# Auxiliary.net
KiCad netlist of a schematic drawn in Altium Designer
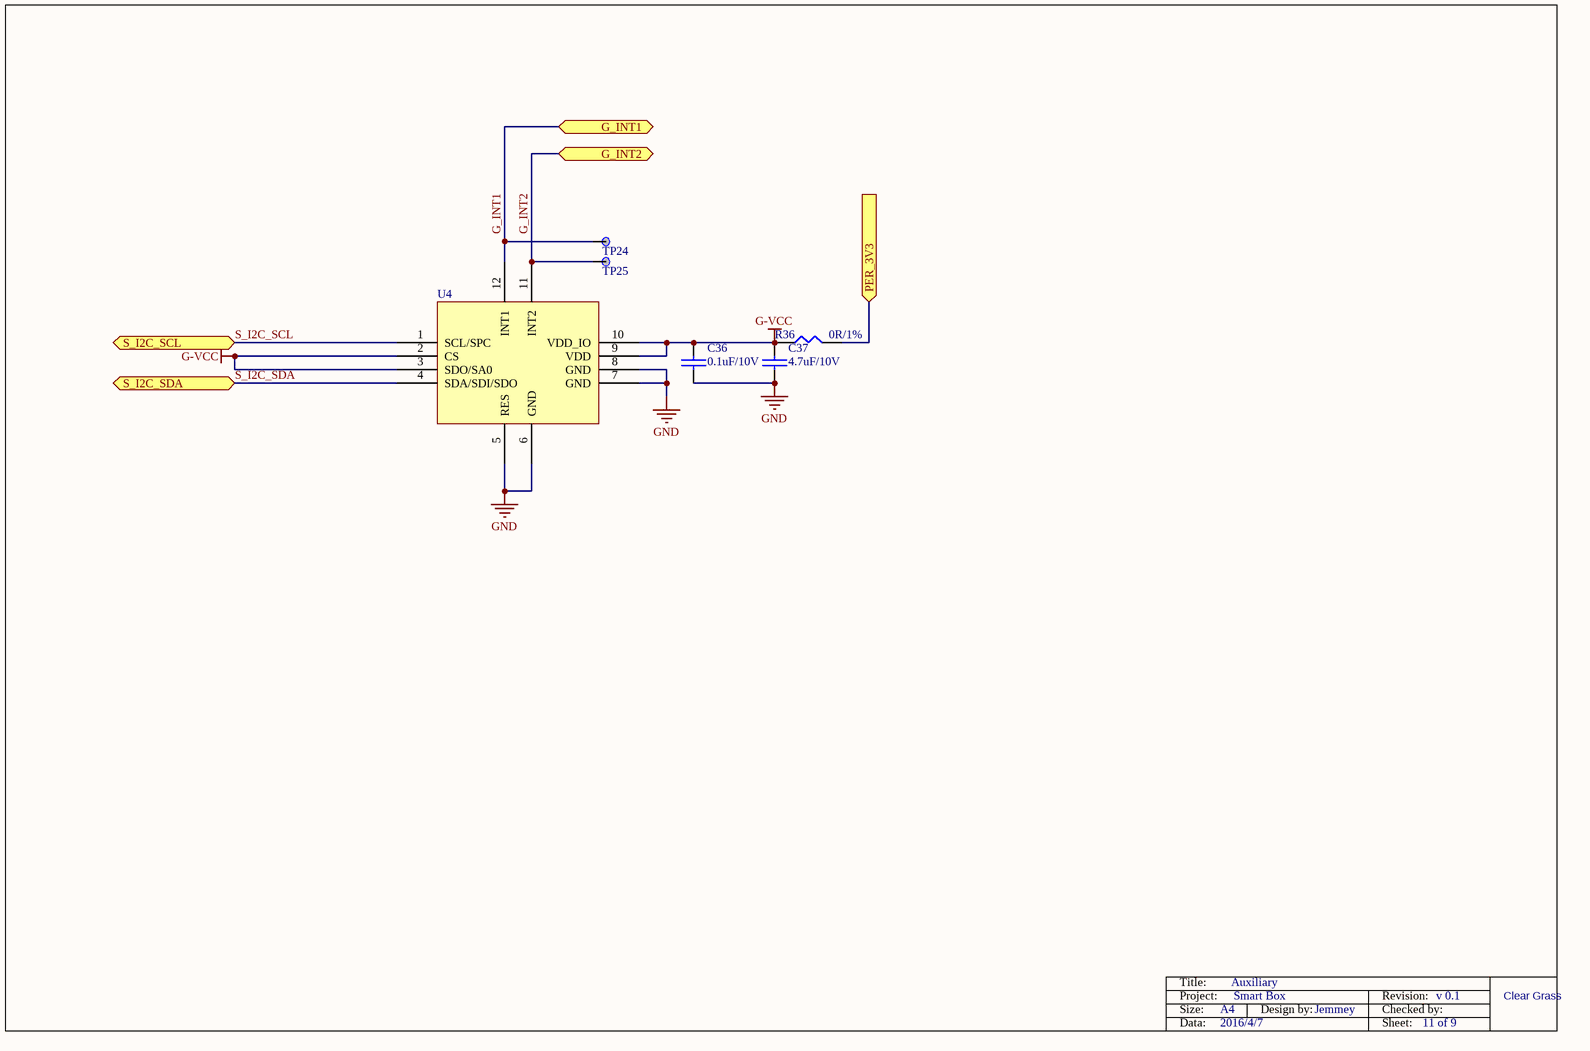
[diagram p0: Auxiliary.SchDoc]

(export (version "E")
  (design (tool "Eeschema 10.0.6"))
  (components
    (comp (ref "C36")
      (value "0.1uF/10V")
      (footprint "0402C")
      (description "厂家：Murata，型号：GRM155R71A104KA01D")
      (libsource (lib "*") (part "CAP"))
    )
    (comp (ref "C37")
      (value "4.7uF/10V")
      (footprint "0603C")
      (description "厂家：Murata，型号：GRM188R61A106KE69D")
      (libsource (lib "*") (part "CAP"))
    )
    (comp (ref "R36")
      (value "0R/1%")
      (footprint "0402R")
      (description "厂家：Yageo，型号：RC0402FR-0710KL")
      (libsource (lib "*") (part "RES1"))
    )
    (comp (ref "TP24") (value "TP") (footprint "TP_C40") (libsource (lib "Almos") (part "TP")))
    (comp (ref "TP25") (value "TP") (footprint "TP_C40") (libsource (lib "Almos") (part "TP")))
    (comp (ref "U4")
      (value "~")
      (description "厂家：ST，型号：LIS2DH12")
      (libsource (lib "Smart Box") (part "LIS2DE12"))
    )
  )
  (nets
    (net (code "1") (name "/G_INT1") (class "Default")
      (node (ref "TP24") (pin "1") (pinfunction "1_1") (pintype "passive"))
      (node (ref "U4") (pin "12") (pinfunction "INT1_12") (pintype "passive"))
    )
    (net (code "2") (name "/G_INT2") (class "Default")
      (node (ref "TP25") (pin "1") (pinfunction "1_1") (pintype "passive"))
      (node (ref "U4") (pin "11") (pinfunction "INT2_11") (pintype "passive"))
    )
    (net (code "3") (name "/PER_3V3") (class "Default")
      (node (ref "R36") (pin "2") (pinfunction "2_2") (pintype "passive"))
    )
    (net (code "4") (name "/S_I2C_SCL") (class "Default")
      (node (ref "U4") (pin "1") (pinfunction "SCL/SPC_1") (pintype "passive"))
    )
    (net (code "5") (name "/S_I2C_SDA") (class "Default")
      (node (ref "U4") (pin "4") (pinfunction "SDA/SDI/SDO_4") (pintype "passive"))
    )
    (net (code "6") (name "G-VCC") (class "Default")
      (node (ref "C36") (pin "1") (pinfunction "1_1") (pintype "passive"))
      (node (ref "C37") (pin "1") (pinfunction "1_1") (pintype "passive"))
      (node (ref "R36") (pin "1") (pinfunction "1_1") (pintype "passive"))
      (node (ref "U4") (pin "10") (pinfunction "VDD_IO_10") (pintype "passive"))
      (node (ref "U4") (pin "2") (pinfunction "CS_2") (pintype "passive"))
      (node (ref "U4") (pin "3") (pinfunction "SDO/SA0_3") (pintype "passive"))
      (node (ref "U4") (pin "9") (pinfunction "VDD_9") (pintype "passive"))
    )
    (net (code "7") (name "GND") (class "Default")
      (node (ref "C36") (pin "2") (pinfunction "2_2") (pintype "passive"))
      (node (ref "C37") (pin "2") (pinfunction "2_2") (pintype "passive"))
      (node (ref "U4") (pin "5") (pinfunction "RES_5") (pintype "passive"))
      (node (ref "U4") (pin "6") (pinfunction "GND_6") (pintype "passive"))
      (node (ref "U4") (pin "7") (pinfunction "GND_7") (pintype "passive"))
      (node (ref "U4") (pin "8") (pinfunction "GND_8") (pintype "passive"))
    )
  )
)
